# avalanch_pulse_gen.net
KiCad netlist of a schematic drawn in EAGLE
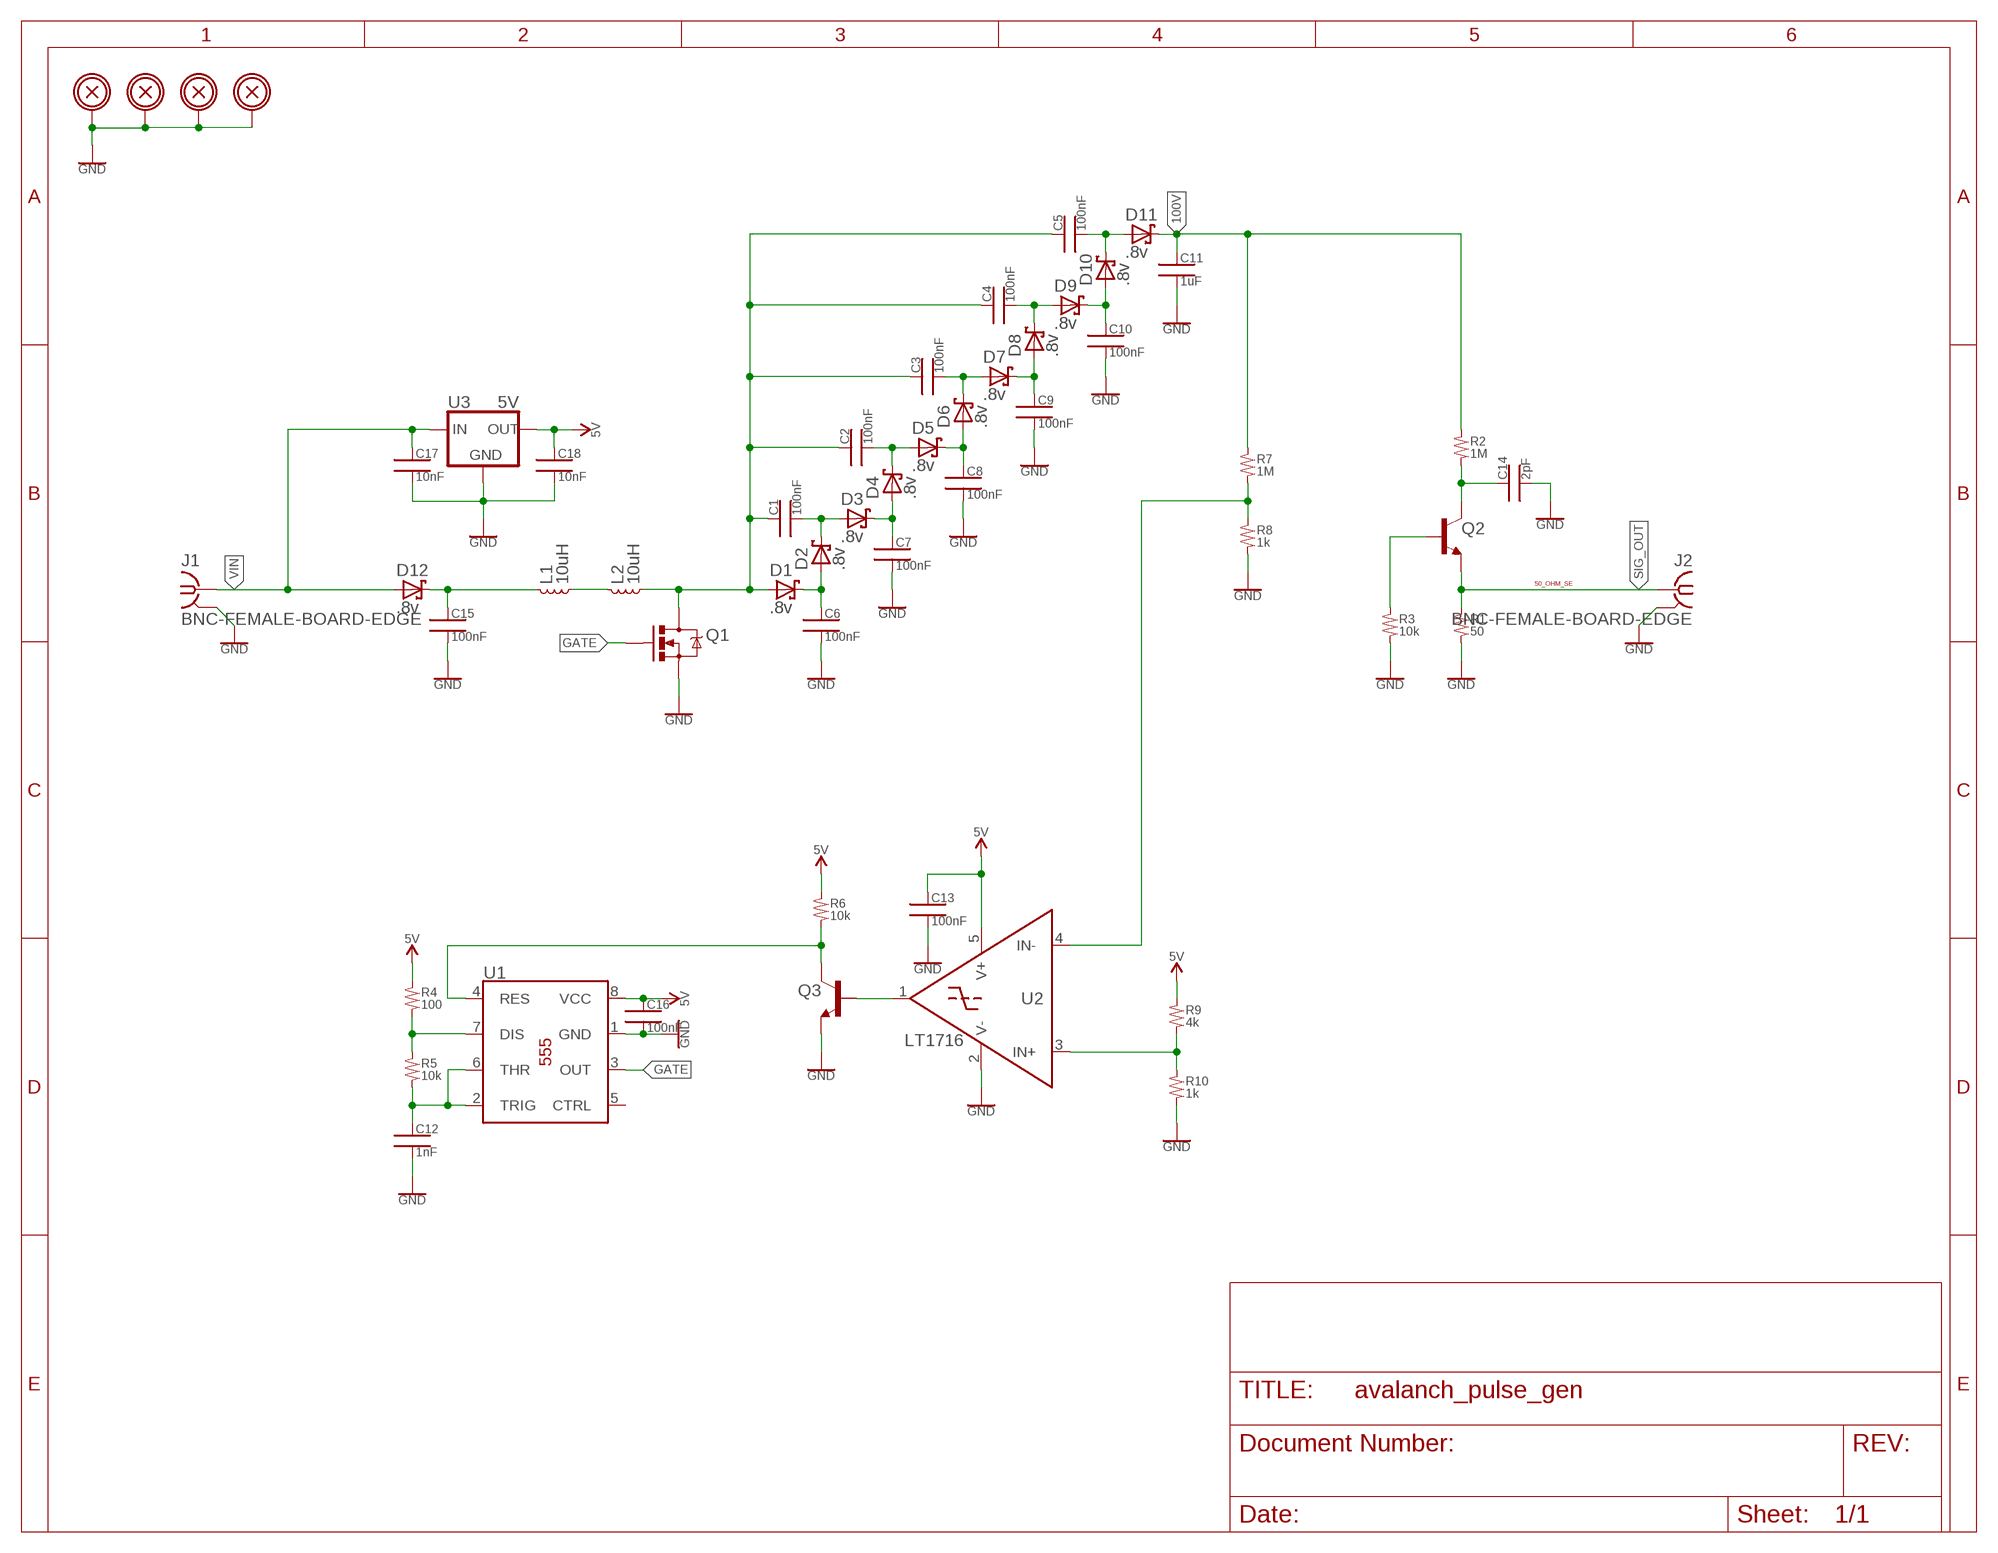
[diagram p0: schematic, sheet 1]

(export (version "E")
  (design (tool "Eeschema 10.0.6"))
  (components
    (comp (ref "C1")
      (value "100nF")
      (footprint "eagle-import:1206")
      (libsource (lib "eagle-import") (part "CAP_SMD_1206"))
    )
    (comp (ref "C2")
      (value "100nF")
      (footprint "eagle-import:1206")
      (libsource (lib "eagle-import") (part "CAP_SMD_1206"))
    )
    (comp (ref "C3")
      (value "100nF")
      (footprint "eagle-import:1206")
      (libsource (lib "eagle-import") (part "CAP_SMD_1206"))
    )
    (comp (ref "C4")
      (value "100nF")
      (footprint "eagle-import:1206")
      (libsource (lib "eagle-import") (part "CAP_SMD_1206"))
    )
    (comp (ref "C5")
      (value "100nF")
      (footprint "eagle-import:1206")
      (libsource (lib "eagle-import") (part "CAP_SMD_1206"))
    )
    (comp (ref "C6")
      (value "100nF")
      (footprint "eagle-import:1206")
      (libsource (lib "eagle-import") (part "CAP_SMD_1206"))
    )
    (comp (ref "C7")
      (value "100nF")
      (footprint "eagle-import:1206")
      (libsource (lib "eagle-import") (part "CAP_SMD_1206"))
    )
    (comp (ref "C8")
      (value "100nF")
      (footprint "eagle-import:1206")
      (libsource (lib "eagle-import") (part "CAP_SMD_1206"))
    )
    (comp (ref "C9")
      (value "100nF")
      (footprint "eagle-import:1206")
      (libsource (lib "eagle-import") (part "CAP_SMD_1206"))
    )
    (comp (ref "C10")
      (value "100nF")
      (footprint "eagle-import:1206")
      (libsource (lib "eagle-import") (part "CAP_SMD_1206"))
    )
    (comp (ref "C11")
      (value "1uF")
      (footprint "eagle-import:2220")
      (libsource (lib "eagle-import") (part "CAP_SMD_2220"))
    )
    (comp (ref "C12")
      (value "1nF")
      (footprint "eagle-import:0402")
      (libsource (lib "eagle-import") (part "CAP_SMD_0402"))
    )
    (comp (ref "C13")
      (value "100nF")
      (footprint "eagle-import:0402")
      (libsource (lib "eagle-import") (part "CAP_SMD_0402"))
    )
    (comp (ref "C14")
      (value "2pF")
      (footprint "eagle-import:0805")
      (libsource (lib "eagle-import") (part "CAP_SMD_0805"))
    )
    (comp (ref "C15")
      (value "100nF")
      (footprint "eagle-import:1206")
      (libsource (lib "eagle-import") (part "CAP_SMD_1206"))
    )
    (comp (ref "C16")
      (value "100nF")
      (footprint "eagle-import:0402")
      (libsource (lib "eagle-import") (part "CAP_SMD_0402"))
    )
    (comp (ref "C17")
      (value "10nF")
      (footprint "eagle-import:0402")
      (libsource (lib "eagle-import") (part "CAP_SMD_0402"))
    )
    (comp (ref "C18")
      (value "10nF")
      (footprint "eagle-import:0402")
      (libsource (lib "eagle-import") (part "CAP_SMD_0402"))
    )
    (comp (ref "D1")
      (value ".8v")
      (footprint "eagle-import:SOD-123")
      (libsource (lib "eagle-import") (part "SCHOTTKY_SOD-123"))
    )
    (comp (ref "D2")
      (value ".8v")
      (footprint "eagle-import:SOD-123")
      (libsource (lib "eagle-import") (part "SCHOTTKY_SOD-123"))
    )
    (comp (ref "D3")
      (value ".8v")
      (footprint "eagle-import:SOD-123")
      (libsource (lib "eagle-import") (part "SCHOTTKY_SOD-123"))
    )
    (comp (ref "D4")
      (value ".8v")
      (footprint "eagle-import:SOD-123")
      (libsource (lib "eagle-import") (part "SCHOTTKY_SOD-123"))
    )
    (comp (ref "D5")
      (value ".8v")
      (footprint "eagle-import:SOD-123")
      (libsource (lib "eagle-import") (part "SCHOTTKY_SOD-123"))
    )
    (comp (ref "D6")
      (value ".8v")
      (footprint "eagle-import:SOD-123")
      (libsource (lib "eagle-import") (part "SCHOTTKY_SOD-123"))
    )
    (comp (ref "D7")
      (value ".8v")
      (footprint "eagle-import:SOD-123")
      (libsource (lib "eagle-import") (part "SCHOTTKY_SOD-123"))
    )
    (comp (ref "D8")
      (value ".8v")
      (footprint "eagle-import:SOD-123")
      (libsource (lib "eagle-import") (part "SCHOTTKY_SOD-123"))
    )
    (comp (ref "D9")
      (value ".8v")
      (footprint "eagle-import:SOD-123")
      (libsource (lib "eagle-import") (part "SCHOTTKY_SOD-123"))
    )
    (comp (ref "D10")
      (value ".8v")
      (footprint "eagle-import:SOD-123")
      (libsource (lib "eagle-import") (part "SCHOTTKY_SOD-123"))
    )
    (comp (ref "D11")
      (value ".8v")
      (footprint "eagle-import:SOD-123")
      (libsource (lib "eagle-import") (part "SCHOTTKY_SOD-123"))
    )
    (comp (ref "D12")
      (value ".8v")
      (footprint "eagle-import:SOD-123")
      (libsource (lib "eagle-import") (part "SCHOTTKY_SOD-123"))
    )
    (comp (ref "H1")
      (value "BOLTHOLE_M2.5")
      (footprint "eagle-import:M2.5_HOLE")
      (libsource (lib "eagle-import") (part "BOLTHOLE_M2.5"))
    )
    (comp (ref "H2")
      (value "BOLTHOLE_M2.5")
      (footprint "eagle-import:M2.5_HOLE")
      (libsource (lib "eagle-import") (part "BOLTHOLE_M2.5"))
    )
    (comp (ref "H3")
      (value "BOLTHOLE_M2.5")
      (footprint "eagle-import:M2.5_HOLE")
      (libsource (lib "eagle-import") (part "BOLTHOLE_M2.5"))
    )
    (comp (ref "H4")
      (value "BOLTHOLE_M2.5")
      (footprint "eagle-import:M2.5_HOLE")
      (libsource (lib "eagle-import") (part "BOLTHOLE_M2.5"))
    )
    (comp (ref "J1")
      (value "BNC-FEMALE-BOARD-EDGE")
      (footprint "eagle-import:AMPHENOL_112640")
      (libsource (lib "eagle-import") (part "BNC-FEMALE-BOARD-EDGE"))
    )
    (comp (ref "J2")
      (value "BNC-FEMALE-BOARD-EDGE")
      (footprint "eagle-import:AMPHENOL_112640")
      (libsource (lib "eagle-import") (part "BNC-FEMALE-BOARD-EDGE"))
    )
    (comp (ref "L1")
      (value "10uH")
      (footprint "eagle-import:WE74405031100")
      (libsource (lib "eagle-import") (part "IND_SMD_WE74405031100"))
    )
    (comp (ref "L2")
      (value "10uH")
      (footprint "eagle-import:WE74405031100")
      (libsource (lib "eagle-import") (part "IND_SMD_WE74405031100"))
    )
    (comp (ref "Q1")
      (value "MOSFET_N-CHANNEL_SOT23-3")
      (footprint "eagle-import:SOT23-3")
      (libsource (lib "eagle-import") (part "MOSFET_N-CHANNEL_SOT23-3"))
    )
    (comp (ref "Q2")
      (value "BJT_NPN")
      (footprint "eagle-import:SOT23-3")
      (libsource (lib "eagle-import") (part "BJT_NPN"))
    )
    (comp (ref "Q3")
      (value "BJT_NPN")
      (footprint "eagle-import:SOT23-3")
      (libsource (lib "eagle-import") (part "BJT_NPN"))
    )
    (comp (ref "R1")
      (value "50")
      (footprint "eagle-import:0402")
      (libsource (lib "eagle-import") (part "RES_SMD_0402"))
    )
    (comp (ref "R2")
      (value "1M")
      (footprint "eagle-import:1206")
      (libsource (lib "eagle-import") (part "RES_SMD_1206"))
    )
    (comp (ref "R3")
      (value "10k")
      (footprint "eagle-import:0402")
      (libsource (lib "eagle-import") (part "RES_SMD_0402"))
    )
    (comp (ref "R4")
      (value "100")
      (footprint "eagle-import:0402")
      (libsource (lib "eagle-import") (part "RES_SMD_0402"))
    )
    (comp (ref "R5")
      (value "10k")
      (footprint "eagle-import:0402")
      (libsource (lib "eagle-import") (part "RES_SMD_0402"))
    )
    (comp (ref "R6")
      (value "10k")
      (footprint "eagle-import:0402")
      (libsource (lib "eagle-import") (part "RES_SMD_0402"))
    )
    (comp (ref "R7")
      (value "1M")
      (footprint "eagle-import:1206")
      (libsource (lib "eagle-import") (part "RES_SMD_1206"))
    )
    (comp (ref "R8")
      (value "1k")
      (footprint "eagle-import:0402")
      (libsource (lib "eagle-import") (part "RES_SMD_0402"))
    )
    (comp (ref "R9")
      (value "4k")
      (footprint "eagle-import:0402")
      (libsource (lib "eagle-import") (part "RES_SMD_0402"))
    )
    (comp (ref "R10")
      (value "1k")
      (footprint "eagle-import:0402")
      (libsource (lib "eagle-import") (part "RES_SMD_0402"))
    )
    (comp (ref "U1")
      (value "555_TIMER_SOIC-8")
      (footprint "eagle-import:SOIC_8")
      (libsource (lib "eagle-import") (part "555_TIMER_SOIC-8"))
    )
    (comp (ref "U2")
      (value "LT1716")
      (footprint "eagle-import:SOT23-5")
      (libsource (lib "eagle-import") (part "LT1716"))
    )
    (comp (ref "U3")
      (value "5V")
      (footprint "eagle-import:SOT233-4")
      (libsource (lib "eagle-import") (part "UAMXX-Q1DCY"))
    )
  )
  (nets
    (net (code "1") (name "5V") (class "Default")
      (node (ref "C13") (pin "1") (pinfunction "1_1") (pintype "passive"))
      (node (ref "C16") (pin "1") (pinfunction "1_1") (pintype "passive"))
      (node (ref "C18") (pin "1") (pinfunction "1_1") (pintype "passive"))
      (node (ref "R4") (pin "1") (pinfunction "1_1") (pintype "passive"))
      (node (ref "R6") (pin "1") (pinfunction "1_1") (pintype "passive"))
      (node (ref "R9") (pin "1") (pinfunction "1_1") (pintype "passive"))
      (node (ref "U1") (pin "8") (pinfunction "VCC_8") (pintype "bidirectional"))
      (node (ref "U2") (pin "5") (pinfunction "V+_5") (pintype "bidirectional"))
      (node (ref "U3") (pin "3") (pinfunction "OUT_3") (pintype "passive"))
    )
    (net (code "2") (name "100V") (class "Default")
      (node (ref "C11") (pin "1") (pinfunction "1_1") (pintype "passive"))
      (node (ref "D11") (pin "1C") (pinfunction "C_1C") (pintype "passive"))
      (node (ref "R2") (pin "1") (pinfunction "1_1") (pintype "passive"))
      (node (ref "R7") (pin "1") (pinfunction "1_1") (pintype "passive"))
    )
    (net (code "3") (name "GATE") (class "Default")
      (node (ref "Q1") (pin "1") (pinfunction "G_1") (pintype "passive"))
      (node (ref "U1") (pin "3") (pinfunction "OUT_3") (pintype "bidirectional"))
    )
    (net (code "4") (name "GND") (class "Default")
      (node (ref "C10") (pin "2") (pinfunction "2_2") (pintype "passive"))
      (node (ref "C11") (pin "2") (pinfunction "2_2") (pintype "passive"))
      (node (ref "C12") (pin "2") (pinfunction "2_2") (pintype "passive"))
      (node (ref "C13") (pin "2") (pinfunction "2_2") (pintype "passive"))
      (node (ref "C14") (pin "2") (pinfunction "2_2") (pintype "passive"))
      (node (ref "C15") (pin "2") (pinfunction "2_2") (pintype "passive"))
      (node (ref "C16") (pin "2") (pinfunction "2_2") (pintype "passive"))
      (node (ref "C17") (pin "2") (pinfunction "2_2") (pintype "passive"))
      (node (ref "C18") (pin "2") (pinfunction "2_2") (pintype "passive"))
      (node (ref "C6") (pin "2") (pinfunction "2_2") (pintype "passive"))
      (node (ref "C7") (pin "2") (pinfunction "2_2") (pintype "passive"))
      (node (ref "C8") (pin "2") (pinfunction "2_2") (pintype "passive"))
      (node (ref "C9") (pin "2") (pinfunction "2_2") (pintype "passive"))
      (node (ref "H1") (pin "P") (pinfunction "P_P") (pintype "bidirectional"))
      (node (ref "H2") (pin "P") (pinfunction "P_P") (pintype "bidirectional"))
      (node (ref "H3") (pin "P") (pinfunction "P_P") (pintype "bidirectional"))
      (node (ref "H4") (pin "P") (pinfunction "P_P") (pintype "bidirectional"))
      (node (ref "J1") (pin "SH1") (pinfunction "GND_SH1") (pintype "power_in"))
      (node (ref "J1") (pin "SH2") (pinfunction "GND_SH2") (pintype "power_in"))
      (node (ref "J1") (pin "SH3") (pinfunction "GND_SH3") (pintype "power_in"))
      (node (ref "J1") (pin "SH4") (pinfunction "GND_SH4") (pintype "power_in"))
      (node (ref "J2") (pin "SH1") (pinfunction "GND_SH1") (pintype "power_in"))
      (node (ref "J2") (pin "SH2") (pinfunction "GND_SH2") (pintype "power_in"))
      (node (ref "J2") (pin "SH3") (pinfunction "GND_SH3") (pintype "power_in"))
      (node (ref "J2") (pin "SH4") (pinfunction "GND_SH4") (pintype "power_in"))
      (node (ref "Q1") (pin "2") (pinfunction "S_2") (pintype "passive"))
      (node (ref "Q3") (pin "2") (pinfunction "E_2") (pintype "passive"))
      (node (ref "R1") (pin "2") (pinfunction "2_2") (pintype "passive"))
      (node (ref "R10") (pin "2") (pinfunction "2_2") (pintype "passive"))
      (node (ref "R3") (pin "2") (pinfunction "2_2") (pintype "passive"))
      (node (ref "R8") (pin "2") (pinfunction "2_2") (pintype "passive"))
      (node (ref "U1") (pin "1") (pinfunction "GND_1") (pintype "bidirectional"))
      (node (ref "U2") (pin "2") (pinfunction "V-_2") (pintype "bidirectional"))
      (node (ref "U3") (pin "2") (pinfunction "GND_2") (pintype "input"))
      (node (ref "U3") (pin "4") (pinfunction "GND_4") (pintype "input"))
    )
    (net (code "5") (name "Net-(D1-A)") (class "Default")
      (node (ref "C1") (pin "1") (pinfunction "1_1") (pintype "passive"))
      (node (ref "C2") (pin "1") (pinfunction "1_1") (pintype "passive"))
      (node (ref "C3") (pin "1") (pinfunction "1_1") (pintype "passive"))
      (node (ref "C4") (pin "1") (pinfunction "1_1") (pintype "passive"))
      (node (ref "C5") (pin "1") (pinfunction "1_1") (pintype "passive"))
      (node (ref "D1") (pin "2A") (pinfunction "A_2A") (pintype "passive"))
      (node (ref "L2") (pin "2") (pinfunction "2_2") (pintype "passive"))
      (node (ref "Q1") (pin "3") (pinfunction "D_3") (pintype "passive"))
    )
    (net (code "6") (name "Net-(D1-C)") (class "Default")
      (node (ref "C6") (pin "1") (pinfunction "1_1") (pintype "passive"))
      (node (ref "D1") (pin "1C") (pinfunction "C_1C") (pintype "passive"))
      (node (ref "D2") (pin "2A") (pinfunction "A_2A") (pintype "passive"))
    )
    (net (code "7") (name "Net-(D2-C)") (class "Default")
      (node (ref "C1") (pin "2") (pinfunction "2_2") (pintype "passive"))
      (node (ref "D2") (pin "1C") (pinfunction "C_1C") (pintype "passive"))
      (node (ref "D3") (pin "2A") (pinfunction "A_2A") (pintype "passive"))
    )
    (net (code "8") (name "Net-(D3-C)") (class "Default")
      (node (ref "C7") (pin "1") (pinfunction "1_1") (pintype "passive"))
      (node (ref "D3") (pin "1C") (pinfunction "C_1C") (pintype "passive"))
      (node (ref "D4") (pin "2A") (pinfunction "A_2A") (pintype "passive"))
    )
    (net (code "9") (name "Net-(D4-C)") (class "Default")
      (node (ref "C2") (pin "2") (pinfunction "2_2") (pintype "passive"))
      (node (ref "D4") (pin "1C") (pinfunction "C_1C") (pintype "passive"))
      (node (ref "D5") (pin "2A") (pinfunction "A_2A") (pintype "passive"))
    )
    (net (code "10") (name "Net-(D5-C)") (class "Default")
      (node (ref "C8") (pin "1") (pinfunction "1_1") (pintype "passive"))
      (node (ref "D5") (pin "1C") (pinfunction "C_1C") (pintype "passive"))
      (node (ref "D6") (pin "2A") (pinfunction "A_2A") (pintype "passive"))
    )
    (net (code "11") (name "Net-(D6-C)") (class "Default")
      (node (ref "C3") (pin "2") (pinfunction "2_2") (pintype "passive"))
      (node (ref "D6") (pin "1C") (pinfunction "C_1C") (pintype "passive"))
      (node (ref "D7") (pin "2A") (pinfunction "A_2A") (pintype "passive"))
    )
    (net (code "12") (name "Net-(D7-C)") (class "Default")
      (node (ref "C9") (pin "1") (pinfunction "1_1") (pintype "passive"))
      (node (ref "D7") (pin "1C") (pinfunction "C_1C") (pintype "passive"))
      (node (ref "D8") (pin "2A") (pinfunction "A_2A") (pintype "passive"))
    )
    (net (code "13") (name "Net-(D8-C)") (class "Default")
      (node (ref "C4") (pin "2") (pinfunction "2_2") (pintype "passive"))
      (node (ref "D8") (pin "1C") (pinfunction "C_1C") (pintype "passive"))
      (node (ref "D9") (pin "2A") (pinfunction "A_2A") (pintype "passive"))
    )
    (net (code "14") (name "Net-(D10-A)") (class "Default")
      (node (ref "C10") (pin "1") (pinfunction "1_1") (pintype "passive"))
      (node (ref "D10") (pin "2A") (pinfunction "A_2A") (pintype "passive"))
      (node (ref "D9") (pin "1C") (pinfunction "C_1C") (pintype "passive"))
    )
    (net (code "15") (name "Net-(D10-C)") (class "Default")
      (node (ref "C5") (pin "2") (pinfunction "2_2") (pintype "passive"))
      (node (ref "D10") (pin "1C") (pinfunction "C_1C") (pintype "passive"))
      (node (ref "D11") (pin "2A") (pinfunction "A_2A") (pintype "passive"))
    )
    (net (code "16") (name "Net-(D12-C)") (class "Default")
      (node (ref "C15") (pin "1") (pinfunction "1_1") (pintype "passive"))
      (node (ref "D12") (pin "1C") (pinfunction "C_1C") (pintype "passive"))
      (node (ref "L1") (pin "1") (pinfunction "1_1") (pintype "passive"))
    )
    (net (code "17") (name "Net-(L1-Pad2)") (class "Default")
      (node (ref "L1") (pin "2") (pinfunction "2_2") (pintype "passive"))
      (node (ref "L2") (pin "1") (pinfunction "1_1") (pintype "passive"))
    )
    (net (code "18") (name "Net-(Q2-B)") (class "Default")
      (node (ref "Q2") (pin "1") (pinfunction "B_1") (pintype "passive"))
      (node (ref "R3") (pin "1") (pinfunction "1_1") (pintype "passive"))
    )
    (net (code "19") (name "Net-(Q2-C)") (class "Default")
      (node (ref "C14") (pin "1") (pinfunction "1_1") (pintype "passive"))
      (node (ref "Q2") (pin "3") (pinfunction "C_3") (pintype "passive"))
      (node (ref "R2") (pin "2") (pinfunction "2_2") (pintype "passive"))
    )
    (net (code "20") (name "Net-(Q3-B)") (class "Default")
      (node (ref "Q3") (pin "1") (pinfunction "B_1") (pintype "passive"))
      (node (ref "U2") (pin "1") (pinfunction "OUT_1") (pintype "bidirectional"))
    )
    (net (code "21") (name "Net-(Q3-C)") (class "Default")
      (node (ref "Q3") (pin "3") (pinfunction "C_3") (pintype "passive"))
      (node (ref "R6") (pin "2") (pinfunction "2_2") (pintype "passive"))
      (node (ref "U1") (pin "4") (pinfunction "RES_4") (pintype "bidirectional"))
    )
    (net (code "22") (name "Net-(U1-DIS)") (class "Default")
      (node (ref "R4") (pin "2") (pinfunction "2_2") (pintype "passive"))
      (node (ref "R5") (pin "1") (pinfunction "1_1") (pintype "passive"))
      (node (ref "U1") (pin "7") (pinfunction "DIS_7") (pintype "bidirectional"))
    )
    (net (code "23") (name "Net-(U1-THR)") (class "Default")
      (node (ref "C12") (pin "1") (pinfunction "1_1") (pintype "passive"))
      (node (ref "R5") (pin "2") (pinfunction "2_2") (pintype "passive"))
      (node (ref "U1") (pin "2") (pinfunction "TRIG_2") (pintype "bidirectional"))
      (node (ref "U1") (pin "6") (pinfunction "THR_6") (pintype "bidirectional"))
    )
    (net (code "24") (name "Net-(U2-IN+)") (class "Default")
      (node (ref "R10") (pin "1") (pinfunction "1_1") (pintype "passive"))
      (node (ref "R9") (pin "2") (pinfunction "2_2") (pintype "passive"))
      (node (ref "U2") (pin "3") (pinfunction "IN+_3") (pintype "bidirectional"))
    )
    (net (code "25") (name "Net-(U2-IN-)") (class "Default")
      (node (ref "R7") (pin "2") (pinfunction "2_2") (pintype "passive"))
      (node (ref "R8") (pin "1") (pinfunction "1_1") (pintype "passive"))
      (node (ref "U2") (pin "4") (pinfunction "IN-_4") (pintype "bidirectional"))
    )
    (net (code "26") (name "SIG_OUT") (class "Default")
      (node (ref "J2") (pin "SIG") (pinfunction "1_SIG") (pintype "passive"))
      (node (ref "Q2") (pin "2") (pinfunction "E_2") (pintype "passive"))
      (node (ref "R1") (pin "1") (pinfunction "1_1") (pintype "passive"))
    )
    (net (code "27") (name "VIN") (class "Default")
      (node (ref "C17") (pin "1") (pinfunction "1_1") (pintype "passive"))
      (node (ref "D12") (pin "2A") (pinfunction "A_2A") (pintype "passive"))
      (node (ref "J1") (pin "SIG") (pinfunction "1_SIG") (pintype "passive"))
      (node (ref "U3") (pin "1") (pinfunction "IN_1") (pintype "input"))
    )
    (net (code "28") (name "unconnected-(U1-CTRL-Pad5)") (class "Default")
      (node (ref "U1") (pin "5") (pinfunction "CTRL_5") (pintype "bidirectional"))
    )
  )
)
